# vaporsound.net
KiCad netlist of a schematic drawn in EAGLE
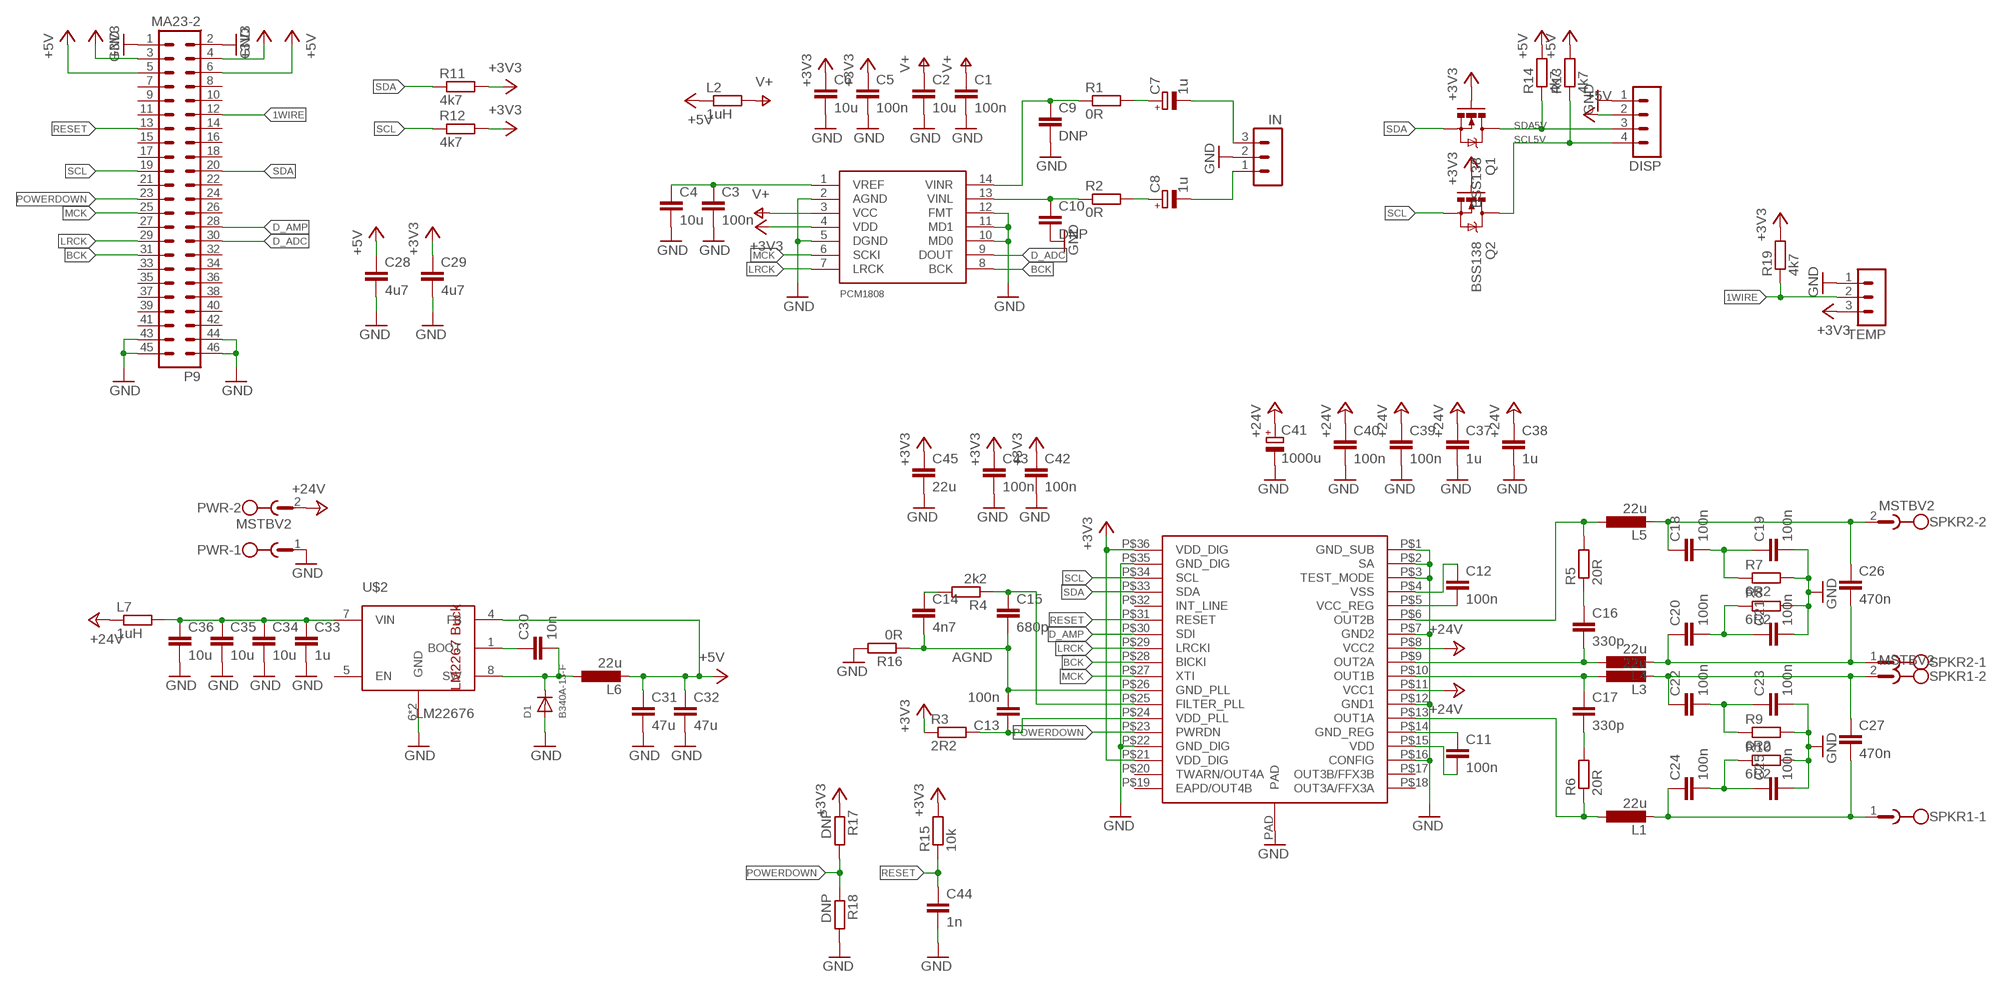
[diagram p0: schematic, sheet 1]

(export (version "E")
  (design (tool "Eeschema 10.0.6"))
  (components
    (comp (ref "C1")
      (value "100n")
      (footprint "eagle-import:C0603")
      (libsource (lib "eagle-import") (part "C-EUC0603"))
    )
    (comp (ref "C2")
      (value "10u")
      (footprint "eagle-import:C0805")
      (libsource (lib "eagle-import") (part "C-EUC0805"))
    )
    (comp (ref "C3")
      (value "100n")
      (footprint "eagle-import:C0603")
      (libsource (lib "eagle-import") (part "C-EUC0603"))
    )
    (comp (ref "C4")
      (value "10u")
      (footprint "eagle-import:C0805")
      (libsource (lib "eagle-import") (part "C-EUC0805"))
    )
    (comp (ref "C5")
      (value "100n")
      (footprint "eagle-import:C0603")
      (libsource (lib "eagle-import") (part "C-EUC0603"))
    )
    (comp (ref "C6")
      (value "10u")
      (footprint "eagle-import:C0805")
      (libsource (lib "eagle-import") (part "C-EUC0805"))
    )
    (comp (ref "C7")
      (value "1u")
      (footprint "eagle-import:E2-5")
      (libsource (lib "eagle-import") (part "CPOL-EUE2-5"))
    )
    (comp (ref "C8")
      (value "1u")
      (footprint "eagle-import:E2-5")
      (libsource (lib "eagle-import") (part "CPOL-EUE2-5"))
    )
    (comp (ref "C9")
      (value "DNP")
      (footprint "eagle-import:C0603")
      (libsource (lib "eagle-import") (part "C-EUC0603"))
    )
    (comp (ref "C10")
      (value "DNP")
      (footprint "eagle-import:C0603")
      (libsource (lib "eagle-import") (part "C-EUC0603"))
    )
    (comp (ref "C11")
      (value "100n")
      (footprint "eagle-import:C0603")
      (libsource (lib "eagle-import") (part "C-EUC0603"))
    )
    (comp (ref "C12")
      (value "100n")
      (footprint "eagle-import:C0603")
      (libsource (lib "eagle-import") (part "C-EUC0603"))
    )
    (comp (ref "C13")
      (value "100n")
      (footprint "eagle-import:C0603")
      (libsource (lib "eagle-import") (part "C-EUC0603"))
    )
    (comp (ref "C14")
      (value "4n7")
      (footprint "eagle-import:C0603")
      (libsource (lib "eagle-import") (part "C-EUC0603"))
    )
    (comp (ref "C15")
      (value "680p")
      (footprint "eagle-import:C0603")
      (libsource (lib "eagle-import") (part "C-EUC0603"))
    )
    (comp (ref "C16")
      (value "330p")
      (footprint "eagle-import:C0603")
      (libsource (lib "eagle-import") (part "C-EUC0603"))
    )
    (comp (ref "C17")
      (value "330p")
      (footprint "eagle-import:C0603")
      (libsource (lib "eagle-import") (part "C-EUC0603"))
    )
    (comp (ref "C18")
      (value "100n")
      (footprint "eagle-import:C0603")
      (libsource (lib "eagle-import") (part "C-EUC0603"))
    )
    (comp (ref "C19")
      (value "100n")
      (footprint "eagle-import:C0603")
      (libsource (lib "eagle-import") (part "C-EUC0603"))
    )
    (comp (ref "C20")
      (value "100n")
      (footprint "eagle-import:C0603")
      (libsource (lib "eagle-import") (part "C-EUC0603"))
    )
    (comp (ref "C21")
      (value "100n")
      (footprint "eagle-import:C0603")
      (libsource (lib "eagle-import") (part "C-EUC0603"))
    )
    (comp (ref "C22")
      (value "100n")
      (footprint "eagle-import:C0603")
      (libsource (lib "eagle-import") (part "C-EUC0603"))
    )
    (comp (ref "C23")
      (value "100n")
      (footprint "eagle-import:C0603")
      (libsource (lib "eagle-import") (part "C-EUC0603"))
    )
    (comp (ref "C24")
      (value "100n")
      (footprint "eagle-import:C0603")
      (libsource (lib "eagle-import") (part "C-EUC0603"))
    )
    (comp (ref "C25")
      (value "100n")
      (footprint "eagle-import:C0603")
      (libsource (lib "eagle-import") (part "C-EUC0603"))
    )
    (comp (ref "C26")
      (value "470n")
      (footprint "eagle-import:C050-045X075")
      (libsource (lib "eagle-import") (part "C-EU050-045X075"))
    )
    (comp (ref "C27")
      (value "470n")
      (footprint "eagle-import:C050-045X075")
      (libsource (lib "eagle-import") (part "C-EU050-045X075"))
    )
    (comp (ref "C28")
      (value "4u7")
      (footprint "eagle-import:C0805")
      (libsource (lib "eagle-import") (part "C-EUC0805"))
    )
    (comp (ref "C29")
      (value "4u7")
      (footprint "eagle-import:C0805")
      (libsource (lib "eagle-import") (part "C-EUC0805"))
    )
    (comp (ref "C30")
      (value "10n")
      (footprint "eagle-import:C0603")
      (libsource (lib "eagle-import") (part "C-EUC0603"))
    )
    (comp (ref "C31")
      (value "47u")
      (footprint "eagle-import:C1206")
      (libsource (lib "eagle-import") (part "C-EUC1206"))
    )
    (comp (ref "C32")
      (value "47u")
      (footprint "eagle-import:C1206")
      (libsource (lib "eagle-import") (part "C-EUC1206"))
    )
    (comp (ref "C33")
      (value "1u")
      (footprint "eagle-import:C0805")
      (libsource (lib "eagle-import") (part "C-EUC0805"))
    )
    (comp (ref "C34")
      (value "10u")
      (footprint "eagle-import:C1206")
      (libsource (lib "eagle-import") (part "C-EUC1206"))
    )
    (comp (ref "C35")
      (value "10u")
      (footprint "eagle-import:C1206")
      (libsource (lib "eagle-import") (part "C-EUC1206"))
    )
    (comp (ref "C36")
      (value "10u")
      (footprint "eagle-import:C1206")
      (libsource (lib "eagle-import") (part "C-EUC1206"))
    )
    (comp (ref "C37")
      (value "1u")
      (footprint "eagle-import:C1206")
      (libsource (lib "eagle-import") (part "C-EUC1206"))
    )
    (comp (ref "C38")
      (value "1u")
      (footprint "eagle-import:C1206")
      (libsource (lib "eagle-import") (part "C-EUC1206"))
    )
    (comp (ref "C39")
      (value "100n")
      (footprint "eagle-import:C0603")
      (libsource (lib "eagle-import") (part "C-EUC0603"))
    )
    (comp (ref "C40")
      (value "100n")
      (footprint "eagle-import:C0603")
      (libsource (lib "eagle-import") (part "C-EUC0603"))
    )
    (comp (ref "C41")
      (value "1000u")
      (footprint "eagle-import:E5-10,5")
      (libsource (lib "eagle-import") (part "CPOL-EUE5-10.5"))
    )
    (comp (ref "C42")
      (value "100n")
      (footprint "eagle-import:C0603")
      (libsource (lib "eagle-import") (part "C-EUC0603"))
    )
    (comp (ref "C43")
      (value "100n")
      (footprint "eagle-import:C0603")
      (libsource (lib "eagle-import") (part "C-EUC0603"))
    )
    (comp (ref "C44")
      (value "1n")
      (footprint "eagle-import:C0603")
      (libsource (lib "eagle-import") (part "C-EUC0603"))
    )
    (comp (ref "C45")
      (value "22u")
      (footprint "eagle-import:C1206")
      (libsource (lib "eagle-import") (part "C-EUC1206"))
    )
    (comp (ref "D1")
      (value "B340A-13-F")
      (footprint "eagle-import:SMADIODE")
      (libsource (lib "eagle-import") (part "DIODESMA"))
    )
    (comp (ref "DISP")
      (value "MA04-1")
      (footprint "eagle-import:MA04-1")
      (libsource (lib "eagle-import") (part "MA04-1"))
    )
    (comp (ref "IN")
      (value "MA03-1")
      (footprint "eagle-import:MA03-1")
      (libsource (lib "eagle-import") (part "MA03-1"))
    )
    (comp (ref "L1")
      (value "22u")
      (footprint "eagle-import:SRR1210")
      (libsource (lib "eagle-import") (part "L-EUSRR1210"))
    )
    (comp (ref "L2")
      (value "1uH")
      (footprint "eagle-import:R0805")
      (libsource (lib "eagle-import") (part "R-EU_R0805"))
    )
    (comp (ref "L3")
      (value "22u")
      (footprint "eagle-import:SRR1210")
      (libsource (lib "eagle-import") (part "L-EUSRR1210"))
    )
    (comp (ref "L4")
      (value "22u")
      (footprint "eagle-import:SRR1210")
      (libsource (lib "eagle-import") (part "L-EUSRR1210"))
    )
    (comp (ref "L5")
      (value "22u")
      (footprint "eagle-import:SRR1210")
      (libsource (lib "eagle-import") (part "L-EUSRR1210"))
    )
    (comp (ref "L6")
      (value "22u")
      (footprint "eagle-import:IHLP-3232DZ-11")
      (libsource (lib "eagle-import") (part "L-EUIHLP-3232DZ-11"))
    )
    (comp (ref "L7")
      (value "1uH")
      (footprint "eagle-import:R0805")
      (libsource (lib "eagle-import") (part "R-EU_R0805"))
    )
    (comp (ref "P9")
      (value "MA23-2")
      (footprint "eagle-import:MA23-2")
      (libsource (lib "eagle-import") (part "MA23-2"))
    )
    (comp (ref "PWR")
      (value "MSTBV2")
      (footprint "eagle-import:MSTBV2")
      (fields (field (name "MPN") "MSTBV 2,5/2-GF-5.08"))
      (libsource (lib "eagle-import") (part "MSTBV2"))
    )
    (comp (ref "Q1")
      (value "BSS138")
      (footprint "eagle-import:SOT23-3")
      (libsource (lib "eagle-import") (part "MOSFET-NCHANNELBSS138"))
    )
    (comp (ref "Q2")
      (value "BSS138")
      (footprint "eagle-import:SOT23-3")
      (libsource (lib "eagle-import") (part "MOSFET-NCHANNELBSS138"))
    )
    (comp (ref "R1")
      (value "0R")
      (footprint "eagle-import:R0603")
      (libsource (lib "eagle-import") (part "R-EU_R0603"))
    )
    (comp (ref "R2")
      (value "0R")
      (footprint "eagle-import:R0603")
      (libsource (lib "eagle-import") (part "R-EU_R0603"))
    )
    (comp (ref "R3")
      (value "2R2")
      (footprint "eagle-import:R0603")
      (libsource (lib "eagle-import") (part "R-EU_R0603"))
    )
    (comp (ref "R4")
      (value "2k2")
      (footprint "eagle-import:R0603")
      (libsource (lib "eagle-import") (part "R-EU_R0603"))
    )
    (comp (ref "R5")
      (value "20R")
      (footprint "eagle-import:R1206")
      (libsource (lib "eagle-import") (part "R-EU_R1206"))
    )
    (comp (ref "R6")
      (value "20R")
      (footprint "eagle-import:R1206")
      (libsource (lib "eagle-import") (part "R-EU_R1206"))
    )
    (comp (ref "R7")
      (value "6R2")
      (footprint "eagle-import:R1206")
      (libsource (lib "eagle-import") (part "R-EU_R1206"))
    )
    (comp (ref "R8")
      (value "6R2")
      (footprint "eagle-import:R1206")
      (libsource (lib "eagle-import") (part "R-EU_R1206"))
    )
    (comp (ref "R9")
      (value "6R2")
      (footprint "eagle-import:R1206")
      (libsource (lib "eagle-import") (part "R-EU_R1206"))
    )
    (comp (ref "R10")
      (value "6R2")
      (footprint "eagle-import:R1206")
      (libsource (lib "eagle-import") (part "R-EU_R1206"))
    )
    (comp (ref "R11")
      (value "4k7")
      (footprint "eagle-import:R0603")
      (libsource (lib "eagle-import") (part "R-EU_R0603"))
    )
    (comp (ref "R12")
      (value "4k7")
      (footprint "eagle-import:R0603")
      (libsource (lib "eagle-import") (part "R-EU_R0603"))
    )
    (comp (ref "R13")
      (value "4k7")
      (footprint "eagle-import:R0603")
      (libsource (lib "eagle-import") (part "R-EU_R0603"))
    )
    (comp (ref "R14")
      (value "4k7")
      (footprint "eagle-import:R0603")
      (libsource (lib "eagle-import") (part "R-EU_R0603"))
    )
    (comp (ref "R15")
      (value "10k")
      (footprint "eagle-import:R0603")
      (libsource (lib "eagle-import") (part "R-EU_R0603"))
    )
    (comp (ref "R16")
      (value "0R")
      (footprint "eagle-import:R0603")
      (libsource (lib "eagle-import") (part "R-EU_R0603"))
    )
    (comp (ref "R17")
      (value "DNP")
      (footprint "eagle-import:R0603")
      (libsource (lib "eagle-import") (part "R-EU_R0603"))
    )
    (comp (ref "R18")
      (value "DNP")
      (footprint "eagle-import:R0603")
      (libsource (lib "eagle-import") (part "R-EU_R0603"))
    )
    (comp (ref "R19")
      (value "4k7")
      (footprint "eagle-import:R0603")
      (libsource (lib "eagle-import") (part "R-EU_R0603"))
    )
    (comp (ref "SPKR1")
      (value "MSTBV2")
      (footprint "eagle-import:MSTBV2")
      (fields (field (name "MPN") "MSTBV 2,5/2-GF-5.08"))
      (libsource (lib "eagle-import") (part "MSTBV2"))
    )
    (comp (ref "SPKR2")
      (value "MSTBV2")
      (footprint "eagle-import:MSTBV2")
      (fields (field (name "MPN") "MSTBV 2,5/2-GF-5.08"))
      (libsource (lib "eagle-import") (part "MSTBV2"))
    )
    (comp (ref "TEMP")
      (value "MA03-1")
      (footprint "eagle-import:MA03-1")
      (libsource (lib "eagle-import") (part "MA03-1"))
    )
    (comp (ref "U$1")
      (value "STA350BW")
      (footprint "eagle-import:POWERSSO-36")
      (libsource (lib "eagle-import") (part "STA350BW"))
    )
    (comp (ref "U$2")
      (value "LM22676")
      (footprint "eagle-import:DDA0008B")
      (libsource (lib "eagle-import") (part "LM2267_123"))
    )
    (comp (ref "U$3")
      (value "PCM1808")
      (footprint "eagle-import:TSSOP14")
      (libsource (lib "eagle-import") (part "PCM1808"))
    )
  )
  (nets
    (net (code "1") (name "+3V3") (class "Default")
      (node (ref "C29") (pin "1") (pinfunction "1_1") (pintype "passive"))
      (node (ref "C42") (pin "1") (pinfunction "1_1") (pintype "passive"))
      (node (ref "C43") (pin "1") (pinfunction "1_1") (pintype "passive"))
      (node (ref "C45") (pin "1") (pinfunction "1_1") (pintype "passive"))
      (node (ref "C5") (pin "1") (pinfunction "1_1") (pintype "passive"))
      (node (ref "C6") (pin "1") (pinfunction "1_1") (pintype "passive"))
      (node (ref "P9") (pin "3") (pinfunction "3_3") (pintype "passive"))
      (node (ref "P9") (pin "4") (pinfunction "4_4") (pintype "passive"))
      (node (ref "Q1") (pin "1") (pinfunction "G_1") (pintype "passive"))
      (node (ref "Q2") (pin "1") (pinfunction "G_1") (pintype "passive"))
      (node (ref "R11") (pin "2") (pinfunction "2_2") (pintype "passive"))
      (node (ref "R12") (pin "2") (pinfunction "2_2") (pintype "passive"))
      (node (ref "R15") (pin "2") (pinfunction "2_2") (pintype "passive"))
      (node (ref "R17") (pin "1") (pinfunction "1_1") (pintype "passive"))
      (node (ref "R19") (pin "2") (pinfunction "2_2") (pintype "passive"))
      (node (ref "R3") (pin "1") (pinfunction "1_1") (pintype "passive"))
      (node (ref "TEMP") (pin "3") (pinfunction "3_3") (pintype "passive"))
      (node (ref "U$1") (pin "P$21") (pinfunction "VDD_DIG_P$21") (pintype "bidirectional"))
      (node (ref "U$1") (pin "P$36") (pinfunction "VDD_DIG_P$36") (pintype "bidirectional"))
      (node (ref "U$3") (pin "4") (pinfunction "VDD_4") (pintype "bidirectional"))
    )
    (net (code "2") (name "+5V") (class "Default")
      (node (ref "C28") (pin "1") (pinfunction "1_1") (pintype "passive"))
      (node (ref "C31") (pin "1") (pinfunction "1_1") (pintype "passive"))
      (node (ref "C32") (pin "1") (pinfunction "1_1") (pintype "passive"))
      (node (ref "DISP") (pin "2") (pinfunction "2_2") (pintype "passive"))
      (node (ref "L2") (pin "1") (pinfunction "1_1") (pintype "passive"))
      (node (ref "L6") (pin "P$2") (pinfunction "2_P$2") (pintype "passive"))
      (node (ref "P9") (pin "5") (pinfunction "5_5") (pintype "passive"))
      (node (ref "P9") (pin "6") (pinfunction "6_6") (pintype "passive"))
      (node (ref "R13") (pin "2") (pinfunction "2_2") (pintype "passive"))
      (node (ref "R14") (pin "2") (pinfunction "2_2") (pintype "passive"))
      (node (ref "U$2") (pin "4") (pinfunction "FB_4") (pintype "input"))
    )
    (net (code "3") (name "+24V") (class "Default")
      (node (ref "C37") (pin "1") (pinfunction "1_1") (pintype "passive"))
      (node (ref "C38") (pin "1") (pinfunction "1_1") (pintype "passive"))
      (node (ref "C39") (pin "1") (pinfunction "1_1") (pintype "passive"))
      (node (ref "C40") (pin "1") (pinfunction "1_1") (pintype "passive"))
      (node (ref "C41") (pin "+") (pinfunction "+_+") (pintype "passive"))
      (node (ref "L7") (pin "1") (pinfunction "1_1") (pintype "passive"))
      (node (ref "PWR") (pin "2") (pinfunction "1_2") (pintype "passive"))
      (node (ref "U$1") (pin "P$11") (pinfunction "VCC1_P$11") (pintype "bidirectional"))
      (node (ref "U$1") (pin "P$8") (pinfunction "VCC2_P$8") (pintype "bidirectional"))
    )
    (net (code "4") (name "/AGND") (class "Default")
      (node (ref "C13") (pin "2") (pinfunction "2_2") (pintype "passive"))
      (node (ref "C14") (pin "2") (pinfunction "2_2") (pintype "passive"))
      (node (ref "C15") (pin "2") (pinfunction "2_2") (pintype "passive"))
      (node (ref "R16") (pin "1") (pinfunction "1_1") (pintype "passive"))
      (node (ref "U$1") (pin "P$26") (pinfunction "GND_PLL_P$26") (pintype "bidirectional"))
    )
    (net (code "5") (name "/SCL5V") (class "Default")
      (node (ref "DISP") (pin "4") (pinfunction "4_4") (pintype "passive"))
      (node (ref "Q2") (pin "3") (pinfunction "D_3") (pintype "passive"))
      (node (ref "R13") (pin "1") (pinfunction "1_1") (pintype "passive"))
    )
    (net (code "6") (name "/SDA5V") (class "Default")
      (node (ref "DISP") (pin "3") (pinfunction "3_3") (pintype "passive"))
      (node (ref "Q1") (pin "3") (pinfunction "D_3") (pintype "passive"))
      (node (ref "R14") (pin "1") (pinfunction "1_1") (pintype "passive"))
    )
    (net (code "7") (name "1WIRE") (class "Default")
      (node (ref "P9") (pin "12") (pinfunction "12_12") (pintype "passive"))
      (node (ref "R19") (pin "1") (pinfunction "1_1") (pintype "passive"))
      (node (ref "TEMP") (pin "2") (pinfunction "2_2") (pintype "passive"))
    )
    (net (code "8") (name "BCK") (class "Default")
      (node (ref "P9") (pin "31") (pinfunction "31_31") (pintype "passive"))
      (node (ref "U$1") (pin "P$28") (pinfunction "BICKI_P$28") (pintype "bidirectional"))
      (node (ref "U$3") (pin "8") (pinfunction "BCK_8") (pintype "bidirectional"))
    )
    (net (code "9") (name "D_ADC") (class "Default")
      (node (ref "P9") (pin "30") (pinfunction "30_30") (pintype "passive"))
      (node (ref "U$3") (pin "9") (pinfunction "DOUT_9") (pintype "bidirectional"))
    )
    (net (code "10") (name "D_AMP") (class "Default")
      (node (ref "P9") (pin "28") (pinfunction "28_28") (pintype "passive"))
      (node (ref "U$1") (pin "P$30") (pinfunction "SDI_P$30") (pintype "bidirectional"))
    )
    (net (code "11") (name "GND") (class "Default")
      (node (ref "C1") (pin "2") (pinfunction "2_2") (pintype "passive"))
      (node (ref "C10") (pin "2") (pinfunction "2_2") (pintype "passive"))
      (node (ref "C19") (pin "2") (pinfunction "2_2") (pintype "passive"))
      (node (ref "C2") (pin "2") (pinfunction "2_2") (pintype "passive"))
      (node (ref "C21") (pin "2") (pinfunction "2_2") (pintype "passive"))
      (node (ref "C23") (pin "2") (pinfunction "2_2") (pintype "passive"))
      (node (ref "C25") (pin "2") (pinfunction "2_2") (pintype "passive"))
      (node (ref "C28") (pin "2") (pinfunction "2_2") (pintype "passive"))
      (node (ref "C29") (pin "2") (pinfunction "2_2") (pintype "passive"))
      (node (ref "C3") (pin "2") (pinfunction "2_2") (pintype "passive"))
      (node (ref "C31") (pin "2") (pinfunction "2_2") (pintype "passive"))
      (node (ref "C32") (pin "2") (pinfunction "2_2") (pintype "passive"))
      (node (ref "C33") (pin "2") (pinfunction "2_2") (pintype "passive"))
      (node (ref "C34") (pin "2") (pinfunction "2_2") (pintype "passive"))
      (node (ref "C35") (pin "2") (pinfunction "2_2") (pintype "passive"))
      (node (ref "C36") (pin "2") (pinfunction "2_2") (pintype "passive"))
      (node (ref "C37") (pin "2") (pinfunction "2_2") (pintype "passive"))
      (node (ref "C38") (pin "2") (pinfunction "2_2") (pintype "passive"))
      (node (ref "C39") (pin "2") (pinfunction "2_2") (pintype "passive"))
      (node (ref "C4") (pin "2") (pinfunction "2_2") (pintype "passive"))
      (node (ref "C40") (pin "2") (pinfunction "2_2") (pintype "passive"))
      (node (ref "C41") (pin "-") (pinfunction "-_-") (pintype "passive"))
      (node (ref "C42") (pin "2") (pinfunction "2_2") (pintype "passive"))
      (node (ref "C43") (pin "2") (pinfunction "2_2") (pintype "passive"))
      (node (ref "C44") (pin "2") (pinfunction "2_2") (pintype "passive"))
      (node (ref "C45") (pin "2") (pinfunction "2_2") (pintype "passive"))
      (node (ref "C5") (pin "2") (pinfunction "2_2") (pintype "passive"))
      (node (ref "C6") (pin "2") (pinfunction "2_2") (pintype "passive"))
      (node (ref "C9") (pin "2") (pinfunction "2_2") (pintype "passive"))
      (node (ref "D1") (pin "A") (pinfunction "A_A") (pintype "passive"))
      (node (ref "DISP") (pin "1") (pinfunction "1_1") (pintype "passive"))
      (node (ref "IN") (pin "2") (pinfunction "2_2") (pintype "passive"))
      (node (ref "P9") (pin "1") (pinfunction "1_1") (pintype "passive"))
      (node (ref "P9") (pin "2") (pinfunction "2_2") (pintype "passive"))
      (node (ref "P9") (pin "43") (pinfunction "43_43") (pintype "passive"))
      (node (ref "P9") (pin "44") (pinfunction "44_44") (pintype "passive"))
      (node (ref "P9") (pin "45") (pinfunction "45_45") (pintype "passive"))
      (node (ref "P9") (pin "46") (pinfunction "46_46") (pintype "passive"))
      (node (ref "PWR") (pin "1") (pinfunction "1_1") (pintype "passive"))
      (node (ref "R10") (pin "2") (pinfunction "2_2") (pintype "passive"))
      (node (ref "R16") (pin "2") (pinfunction "2_2") (pintype "passive"))
      (node (ref "R18") (pin "2") (pinfunction "2_2") (pintype "passive"))
      (node (ref "R7") (pin "2") (pinfunction "2_2") (pintype "passive"))
      (node (ref "R8") (pin "2") (pinfunction "2_2") (pintype "passive"))
      (node (ref "R9") (pin "2") (pinfunction "2_2") (pintype "passive"))
      (node (ref "TEMP") (pin "1") (pinfunction "1_1") (pintype "passive"))
      (node (ref "U$1") (pin "P$1") (pinfunction "GND_SUB_P$1") (pintype "bidirectional"))
      (node (ref "U$1") (pin "P$12") (pinfunction "GND1_P$12") (pintype "bidirectional"))
      (node (ref "U$1") (pin "P$16") (pinfunction "CONFIG_P$16") (pintype "bidirectional"))
      (node (ref "U$1") (pin "P$2") (pinfunction "SA_P$2") (pintype "bidirectional"))
      (node (ref "U$1") (pin "P$22") (pinfunction "GND_DIG_P$22") (pintype "bidirectional"))
      (node (ref "U$1") (pin "P$3") (pinfunction "TEST_MODE_P$3") (pintype "bidirectional"))
      (node (ref "U$1") (pin "P$35") (pinfunction "GND_DIG_P$35") (pintype "bidirectional"))
      (node (ref "U$1") (pin "P$7") (pinfunction "GND2_P$7") (pintype "bidirectional"))
      (node (ref "U$1") (pin "PAD") (pinfunction "PAD_PAD") (pintype "bidirectional"))
      (node (ref "U$2") (pin "6") (pinfunction "GND_6") (pintype "power_in"))
      (node (ref "U$2") (pin "EPAD") (pinfunction "GND_EPAD") (pintype "power_in"))
      (node (ref "U$3") (pin "10") (pinfunction "MD0_10") (pintype "bidirectional"))
      (node (ref "U$3") (pin "11") (pinfunction "MD1_11") (pintype "bidirectional"))
      (node (ref "U$3") (pin "12") (pinfunction "FMT_12") (pintype "bidirectional"))
      (node (ref "U$3") (pin "2") (pinfunction "AGND_2") (pintype "bidirectional"))
      (node (ref "U$3") (pin "5") (pinfunction "DGND_5") (pintype "bidirectional"))
    )
    (net (code "12") (name "LRCK") (class "Default")
      (node (ref "P9") (pin "29") (pinfunction "29_29") (pintype "passive"))
      (node (ref "U$1") (pin "P$29") (pinfunction "LRCKI_P$29") (pintype "bidirectional"))
      (node (ref "U$3") (pin "7") (pinfunction "LRCK_7") (pintype "bidirectional"))
    )
    (net (code "13") (name "MCK") (class "Default")
      (node (ref "P9") (pin "25") (pinfunction "25_25") (pintype "passive"))
      (node (ref "U$1") (pin "P$27") (pinfunction "XTI_P$27") (pintype "bidirectional"))
      (node (ref "U$3") (pin "6") (pinfunction "SCKI_6") (pintype "bidirectional"))
    )
    (net (code "14") (name "Net-(C7-Pad+)") (class "Default")
      (node (ref "C7") (pin "+") (pinfunction "+_+") (pintype "passive"))
      (node (ref "R1") (pin "2") (pinfunction "2_2") (pintype "passive"))
    )
    (net (code "15") (name "Net-(C7-Pad-)") (class "Default")
      (node (ref "C7") (pin "-") (pinfunction "-_-") (pintype "passive"))
      (node (ref "IN") (pin "3") (pinfunction "3_3") (pintype "passive"))
    )
    (net (code "16") (name "Net-(C8-Pad+)") (class "Default")
      (node (ref "C8") (pin "+") (pinfunction "+_+") (pintype "passive"))
      (node (ref "R2") (pin "2") (pinfunction "2_2") (pintype "passive"))
    )
    (net (code "17") (name "Net-(C8-Pad-)") (class "Default")
      (node (ref "C8") (pin "-") (pinfunction "-_-") (pintype "passive"))
      (node (ref "IN") (pin "1") (pinfunction "1_1") (pintype "passive"))
    )
    (net (code "18") (name "Net-(C14-Pad1)") (class "Default")
      (node (ref "C14") (pin "1") (pinfunction "1_1") (pintype "passive"))
      (node (ref "R4") (pin "2") (pinfunction "2_2") (pintype "passive"))
    )
    (net (code "19") (name "Net-(C16-Pad1)") (class "Default")
      (node (ref "C16") (pin "1") (pinfunction "1_1") (pintype "passive"))
      (node (ref "R5") (pin "1") (pinfunction "1_1") (pintype "passive"))
    )
    (net (code "20") (name "Net-(C17-Pad2)") (class "Default")
      (node (ref "C17") (pin "2") (pinfunction "2_2") (pintype "passive"))
      (node (ref "R6") (pin "2") (pinfunction "2_2") (pintype "passive"))
    )
    (net (code "21") (name "Net-(C18-Pad2)") (class "Default")
      (node (ref "C18") (pin "2") (pinfunction "2_2") (pintype "passive"))
      (node (ref "C19") (pin "1") (pinfunction "1_1") (pintype "passive"))
      (node (ref "R7") (pin "1") (pinfunction "1_1") (pintype "passive"))
    )
    (net (code "22") (name "Net-(C20-Pad2)") (class "Default")
      (node (ref "C20") (pin "2") (pinfunction "2_2") (pintype "passive"))
      (node (ref "C21") (pin "1") (pinfunction "1_1") (pintype "passive"))
      (node (ref "R8") (pin "1") (pinfunction "1_1") (pintype "passive"))
    )
    (net (code "23") (name "Net-(C22-Pad2)") (class "Default")
      (node (ref "C22") (pin "2") (pinfunction "2_2") (pintype "passive"))
      (node (ref "C23") (pin "1") (pinfunction "1_1") (pintype "passive"))
      (node (ref "R9") (pin "1") (pinfunction "1_1") (pintype "passive"))
    )
    (net (code "24") (name "Net-(C24-Pad2)") (class "Default")
      (node (ref "C24") (pin "2") (pinfunction "2_2") (pintype "passive"))
      (node (ref "C25") (pin "1") (pinfunction "1_1") (pintype "passive"))
      (node (ref "R10") (pin "1") (pinfunction "1_1") (pintype "passive"))
    )
    (net (code "25") (name "Net-(L1-1)") (class "Default")
      (node (ref "L1") (pin "P$1") (pinfunction "1_P$1") (pintype "passive"))
      (node (ref "R6") (pin "1") (pinfunction "1_1") (pintype "passive"))
      (node (ref "U$1") (pin "P$13") (pinfunction "OUT1A_P$13") (pintype "bidirectional"))
    )
    (net (code "26") (name "Net-(L1-2)") (class "Default")
      (node (ref "C24") (pin "1") (pinfunction "1_1") (pintype "passive"))
      (node (ref "C27") (pin "2") (pinfunction "2_2") (pintype "passive"))
      (node (ref "L1") (pin "P$2") (pinfunction "2_P$2") (pintype "passive"))
      (node (ref "SPKR1") (pin "1") (pinfunction "1_1") (pintype "passive"))
    )
    (net (code "27") (name "Net-(L3-1)") (class "Default")
      (node (ref "C17") (pin "1") (pinfunction "1_1") (pintype "passive"))
      (node (ref "L3") (pin "P$1") (pinfunction "1_P$1") (pintype "passive"))
      (node (ref "U$1") (pin "P$10") (pinfunction "OUT1B_P$10") (pintype "bidirectional"))
    )
    (net (code "28") (name "Net-(L3-2)") (class "Default")
      (node (ref "C22") (pin "1") (pinfunction "1_1") (pintype "passive"))
      (node (ref "C27") (pin "1") (pinfunction "1_1") (pintype "passive"))
      (node (ref "L3") (pin "P$2") (pinfunction "2_P$2") (pintype "passive"))
      (node (ref "SPKR1") (pin "2") (pinfunction "1_2") (pintype "passive"))
    )
    (net (code "29") (name "Net-(L4-1)") (class "Default")
      (node (ref "C16") (pin "2") (pinfunction "2_2") (pintype "passive"))
      (node (ref "L4") (pin "P$1") (pinfunction "1_P$1") (pintype "passive"))
      (node (ref "U$1") (pin "P$9") (pinfunction "OUT2A_P$9") (pintype "bidirectional"))
    )
    (net (code "30") (name "Net-(L4-2)") (class "Default")
      (node (ref "C20") (pin "1") (pinfunction "1_1") (pintype "passive"))
      (node (ref "C26") (pin "2") (pinfunction "2_2") (pintype "passive"))
      (node (ref "L4") (pin "P$2") (pinfunction "2_P$2") (pintype "passive"))
      (node (ref "SPKR2") (pin "1") (pinfunction "1_1") (pintype "passive"))
    )
    (net (code "31") (name "Net-(L5-1)") (class "Default")
      (node (ref "L5") (pin "P$1") (pinfunction "1_P$1") (pintype "passive"))
      (node (ref "R5") (pin "2") (pinfunction "2_2") (pintype "passive"))
      (node (ref "U$1") (pin "P$6") (pinfunction "OUT2B_P$6") (pintype "bidirectional"))
    )
    (net (code "32") (name "Net-(L5-2)") (class "Default")
      (node (ref "C18") (pin "1") (pinfunction "1_1") (pintype "passive"))
      (node (ref "C26") (pin "1") (pinfunction "1_1") (pintype "passive"))
      (node (ref "L5") (pin "P$2") (pinfunction "2_P$2") (pintype "passive"))
      (node (ref "SPKR2") (pin "2") (pinfunction "1_2") (pintype "passive"))
    )
    (net (code "33") (name "Net-(L6-1)") (class "Default")
      (node (ref "C30") (pin "2") (pinfunction "2_2") (pintype "passive"))
      (node (ref "D1") (pin "C") (pinfunction "C_C") (pintype "passive"))
      (node (ref "L6") (pin "P$1") (pinfunction "1_P$1") (pintype "passive"))
      (node (ref "U$2") (pin "8") (pinfunction "SW_8") (pintype "power_in"))
    )
    (net (code "34") (name "Net-(U$1-FILTER_PLL)") (class "Default")
      (node (ref "C15") (pin "1") (pinfunction "1_1") (pintype "passive"))
      (node (ref "R4") (pin "1") (pinfunction "1_1") (pintype "passive"))
      (node (ref "U$1") (pin "P$25") (pinfunction "FILTER_PLL_P$25") (pintype "bidirectional"))
    )
    (net (code "35") (name "Net-(U$1-GND_REG)") (class "Default")
      (node (ref "C11") (pin "1") (pinfunction "1_1") (pintype "passive"))
      (node (ref "U$1") (pin "P$14") (pinfunction "GND_REG_P$14") (pintype "bidirectional"))
    )
    (net (code "36") (name "Net-(U$1-VCC_REG)") (class "Default")
      (node (ref "C12") (pin "2") (pinfunction "2_2") (pintype "passive"))
      (node (ref "U$1") (pin "P$5") (pinfunction "VCC_REG_P$5") (pintype "bidirectional"))
    )
    (net (code "37") (name "Net-(U$1-VDD)") (class "Default")
      (node (ref "C11") (pin "2") (pinfunction "2_2") (pintype "passive"))
      (node (ref "U$1") (pin "P$15") (pinfunction "VDD_P$15") (pintype "bidirectional"))
    )
    (net (code "38") (name "Net-(U$1-VDD_PLL)") (class "Default")
      (node (ref "C13") (pin "1") (pinfunction "1_1") (pintype "passive"))
      (node (ref "R3") (pin "2") (pinfunction "2_2") (pintype "passive"))
      (node (ref "U$1") (pin "P$24") (pinfunction "VDD_PLL_P$24") (pintype "bidirectional"))
    )
    (net (code "39") (name "Net-(U$1-VSS)") (class "Default")
      (node (ref "C12") (pin "1") (pinfunction "1_1") (pintype "passive"))
      (node (ref "U$1") (pin "P$4") (pinfunction "VSS_P$4") (pintype "bidirectional"))
    )
    (net (code "40") (name "Net-(U$2-BOOT)") (class "Default")
      (node (ref "C30") (pin "1") (pinfunction "1_1") (pintype "passive"))
      (node (ref "U$2") (pin "1") (pinfunction "BOOT_1") (pintype "power_in"))
    )
    (net (code "41") (name "Net-(U$2-VIN)") (class "Default")
      (node (ref "C33") (pin "1") (pinfunction "1_1") (pintype "passive"))
      (node (ref "C34") (pin "1") (pinfunction "1_1") (pintype "passive"))
      (node (ref "C35") (pin "1") (pinfunction "1_1") (pintype "passive"))
      (node (ref "C36") (pin "1") (pinfunction "1_1") (pintype "passive"))
      (node (ref "L7") (pin "2") (pinfunction "2_2") (pintype "passive"))
      (node (ref "U$2") (pin "7") (pinfunction "VIN_7") (pintype "power_in"))
    )
    (net (code "42") (name "Net-(U$3-VINL)") (class "Default")
      (node (ref "C10") (pin "1") (pinfunction "1_1") (pintype "passive"))
      (node (ref "R2") (pin "1") (pinfunction "1_1") (pintype "passive"))
      (node (ref "U$3") (pin "13") (pinfunction "VINL_13") (pintype "bidirectional"))
    )
    (net (code "43") (name "Net-(U$3-VINR)") (class "Default")
      (node (ref "C9") (pin "1") (pinfunction "1_1") (pintype "passive"))
      (node (ref "R1") (pin "1") (pinfunction "1_1") (pintype "passive"))
      (node (ref "U$3") (pin "14") (pinfunction "VINR_14") (pintype "bidirectional"))
    )
    (net (code "44") (name "Net-(U$3-VREF)") (class "Default")
      (node (ref "C3") (pin "1") (pinfunction "1_1") (pintype "passive"))
      (node (ref "C4") (pin "1") (pinfunction "1_1") (pintype "passive"))
      (node (ref "U$3") (pin "1") (pinfunction "VREF_1") (pintype "bidirectional"))
    )
    (net (code "45") (name "POWERDOWN") (class "Default")
      (node (ref "P9") (pin "23") (pinfunction "23_23") (pintype "passive"))
      (node (ref "R17") (pin "2") (pinfunction "2_2") (pintype "passive"))
      (node (ref "R18") (pin "1") (pinfunction "1_1") (pintype "passive"))
      (node (ref "U$1") (pin "P$23") (pinfunction "PWRDN_P$23") (pintype "bidirectional"))
    )
    (net (code "46") (name "RESET") (class "Default")
      (node (ref "C44") (pin "1") (pinfunction "1_1") (pintype "passive"))
      (node (ref "P9") (pin "13") (pinfunction "13_13") (pintype "passive"))
      (node (ref "R15") (pin "1") (pinfunction "1_1") (pintype "passive"))
      (node (ref "U$1") (pin "P$31") (pinfunction "RESET_P$31") (pintype "bidirectional"))
    )
    (net (code "47") (name "SCL") (class "Default")
      (node (ref "P9") (pin "19") (pinfunction "19_19") (pintype "passive"))
      (node (ref "Q2") (pin "2") (pinfunction "S_2") (pintype "passive"))
      (node (ref "R12") (pin "1") (pinfunction "1_1") (pintype "passive"))
      (node (ref "U$1") (pin "P$34") (pinfunction "SCL_P$34") (pintype "bidirectional"))
    )
    (net (code "48") (name "SDA") (class "Default")
      (node (ref "P9") (pin "20") (pinfunction "20_20") (pintype "passive"))
      (node (ref "Q1") (pin "2") (pinfunction "S_2") (pintype "passive"))
      (node (ref "R11") (pin "1") (pinfunction "1_1") (pintype "passive"))
      (node (ref "U$1") (pin "P$33") (pinfunction "SDA_P$33") (pintype "bidirectional"))
    )
    (net (code "49") (name "V+") (class "Default")
      (node (ref "C1") (pin "1") (pinfunction "1_1") (pintype "passive"))
      (node (ref "C2") (pin "1") (pinfunction "1_1") (pintype "passive"))
      (node (ref "L2") (pin "2") (pinfunction "2_2") (pintype "passive"))
      (node (ref "U$3") (pin "3") (pinfunction "VCC_3") (pintype "bidirectional"))
    )
    (net (code "50") (name "unconnected-(P9-Pad7)") (class "Default")
      (node (ref "P9") (pin "7") (pinfunction "7_7") (pintype "passive"))
    )
    (net (code "51") (name "unconnected-(P9-Pad8)") (class "Default")
      (node (ref "P9") (pin "8") (pinfunction "8_8") (pintype "passive"))
    )
    (net (code "52") (name "unconnected-(P9-Pad9)") (class "Default")
      (node (ref "P9") (pin "9") (pinfunction "9_9") (pintype "passive"))
    )
    (net (code "53") (name "unconnected-(P9-Pad10)") (class "Default")
      (node (ref "P9") (pin "10") (pinfunction "10_10") (pintype "passive"))
    )
    (net (code "54") (name "unconnected-(P9-Pad11)") (class "Default")
      (node (ref "P9") (pin "11") (pinfunction "11_11") (pintype "passive"))
    )
    (net (code "55") (name "unconnected-(P9-Pad14)") (class "Default")
      (node (ref "P9") (pin "14") (pinfunction "14_14") (pintype "passive"))
    )
    (net (code "56") (name "unconnected-(P9-Pad15)") (class "Default")
      (node (ref "P9") (pin "15") (pinfunction "15_15") (pintype "passive"))
    )
    (net (code "57") (name "unconnected-(P9-Pad16)") (class "Default")
      (node (ref "P9") (pin "16") (pinfunction "16_16") (pintype "passive"))
    )
    (net (code "58") (name "unconnected-(P9-Pad17)") (class "Default")
      (node (ref "P9") (pin "17") (pinfunction "17_17") (pintype "passive"))
    )
    (net (code "59") (name "unconnected-(P9-Pad18)") (class "Default")
      (node (ref "P9") (pin "18") (pinfunction "18_18") (pintype "passive"))
    )
    (net (code "60") (name "unconnected-(P9-Pad21)") (class "Default")
      (node (ref "P9") (pin "21") (pinfunction "21_21") (pintype "passive"))
    )
    (net (code "61") (name "unconnected-(P9-Pad22)") (class "Default")
      (node (ref "P9") (pin "22") (pinfunction "22_22") (pintype "passive"))
    )
    (net (code "62") (name "unconnected-(P9-Pad24)") (class "Default")
      (node (ref "P9") (pin "24") (pinfunction "24_24") (pintype "passive"))
    )
    (net (code "63") (name "unconnected-(P9-Pad26)") (class "Default")
      (node (ref "P9") (pin "26") (pinfunction "26_26") (pintype "passive"))
    )
    (net (code "64") (name "unconnected-(P9-Pad27)") (class "Default")
      (node (ref "P9") (pin "27") (pinfunction "27_27") (pintype "passive"))
    )
    (net (code "65") (name "unconnected-(P9-Pad32)") (class "Default")
      (node (ref "P9") (pin "32") (pinfunction "32_32") (pintype "passive"))
    )
    (net (code "66") (name "unconnected-(P9-Pad33)") (class "Default")
      (node (ref "P9") (pin "33") (pinfunction "33_33") (pintype "passive"))
    )
    (net (code "67") (name "unconnected-(P9-Pad34)") (class "Default")
      (node (ref "P9") (pin "34") (pinfunction "34_34") (pintype "passive"))
    )
    (net (code "68") (name "unconnected-(P9-Pad35)") (class "Default")
      (node (ref "P9") (pin "35") (pinfunction "35_35") (pintype "passive"))
    )
    (net (code "69") (name "unconnected-(P9-Pad36)") (class "Default")
      (node (ref "P9") (pin "36") (pinfunction "36_36") (pintype "passive"))
    )
    (net (code "70") (name "unconnected-(P9-Pad37)") (class "Default")
      (node (ref "P9") (pin "37") (pinfunction "37_37") (pintype "passive"))
    )
    (net (code "71") (name "unconnected-(P9-Pad38)") (class "Default")
      (node (ref "P9") (pin "38") (pinfunction "38_38") (pintype "passive"))
    )
    (net (code "72") (name "unconnected-(P9-Pad39)") (class "Default")
      (node (ref "P9") (pin "39") (pinfunction "39_39") (pintype "passive"))
    )
    (net (code "73") (name "unconnected-(P9-Pad40)") (class "Default")
      (node (ref "P9") (pin "40") (pinfunction "40_40") (pintype "passive"))
    )
    (net (code "74") (name "unconnected-(P9-Pad41)") (class "Default")
      (node (ref "P9") (pin "41") (pinfunction "41_41") (pintype "passive"))
    )
    (net (code "75") (name "unconnected-(P9-Pad42)") (class "Default")
      (node (ref "P9") (pin "42") (pinfunction "42_42") (pintype "passive"))
    )
    (net (code "76") (name "unconnected-(U$1-EAPD{slash}OUT4B-PadP$19)") (class "Default")
      (node (ref "U$1") (pin "P$19") (pinfunction "EAPD/OUT4B_P$19") (pintype "bidirectional"))
    )
    (net (code "77") (name "unconnected-(U$1-INT_LINE-PadP$32)") (class "Default")
      (node (ref "U$1") (pin "P$32") (pinfunction "INT_LINE_P$32") (pintype "bidirectional"))
    )
    (net (code "78") (name "unconnected-(U$1-OUT3A{slash}FFX3A-PadP$18)") (class "Default")
      (node (ref "U$1") (pin "P$18") (pinfunction "OUT3A/FFX3A_P$18") (pintype "bidirectional"))
    )
    (net (code "79") (name "unconnected-(U$1-OUT3B{slash}FFX3B-PadP$17)") (class "Default")
      (node (ref "U$1") (pin "P$17") (pinfunction "OUT3B/FFX3B_P$17") (pintype "bidirectional"))
    )
    (net (code "80") (name "unconnected-(U$1-TWARN{slash}OUT4A-PadP$20)") (class "Default")
      (node (ref "U$1") (pin "P$20") (pinfunction "TWARN/OUT4A_P$20") (pintype "bidirectional"))
    )
    (net (code "81") (name "unconnected-(U$2-EN-Pad5)") (class "Default")
      (node (ref "U$2") (pin "5") (pinfunction "EN_5") (pintype "input"))
    )
  )
)
